# Laser_module_supply.net
KiCad netlist of a schematic drawn in Altium Designer
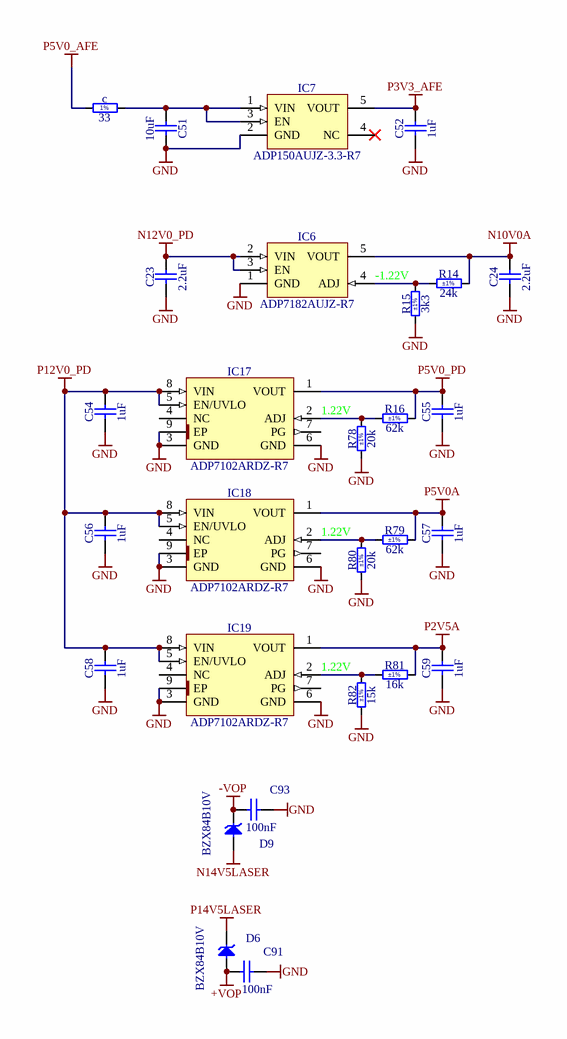
[diagram p0: Laser_module_supply.schdoc]

(export (version "E")
  (design (tool "Eeschema 10.0.6"))
  (components
    (comp (ref "c")
      (value "33")
      (footprint "RESC1005X40N")
      (description "Resistor - 1%")
      (fields
        (field (name "PART NUMBER") "R0402_33R_1%_0.0625W_100PPM")
        (field (name "POWER") "0.0625W")
        (field (name "AUTHOR") "CERN DEM JLC")
      )
      (libsource (lib "Resistors") (part "Resistor - 1%"))
    )
    (comp (ref "C23")
      (value "2.2uF")
      (footprint "CAPC2012X135N")
      (description "Non-polarised capacitor")
      (fields
        (field (name "PART NUMBER") "CC0805_2.2UF_16V_10%_X7R")
        (field (name "VOLTAGE") "16V")
        (field (name "AUTHOR") "CERN DEM JLC")
      )
      (libsource (lib "Capacitors") (part "Capacitor - non polarized"))
    )
    (comp (ref "C24")
      (value "2.2uF")
      (footprint "CAPC2012X135N")
      (description "Non-polarised capacitor")
      (fields
        (field (name "PART NUMBER") "CC0805_2.2UF_16V_10%_X7R")
        (field (name "VOLTAGE") "16V")
        (field (name "AUTHOR") "CERN DEM JLC")
      )
      (libsource (lib "Capacitors") (part "Capacitor - non polarized"))
    )
    (comp (ref "C51")
      (value "10uF")
      (footprint "CAPC2012X135N")
      (description "Non-polarised capacitor")
      (fields
        (field (name "PART NUMBER") "CC0805_10UF_16V_10%_X5R")
        (field (name "VOLTAGE") "16V")
        (field (name "AUTHOR") "CERN DEM JLC")
      )
      (libsource (lib "Capacitors") (part "Capacitor - non polarized"))
    )
    (comp (ref "C52")
      (value "1uF")
      (footprint "CAPC1608X87N")
      (description "Non-polarised capacitor")
      (fields
        (field (name "PART NUMBER") "CC0603_1UF_25V_10%_X7R")
        (field (name "VOLTAGE") "25V")
        (field (name "AUTHOR") "CERN DEM JLC")
      )
      (libsource (lib "Capacitors") (part "Capacitor - non polarized"))
    )
    (comp (ref "C54")
      (value "1uF")
      (footprint "CAPC1608X87N")
      (description "Non-polarised capacitor")
      (fields
        (field (name "PART NUMBER") "CC0603_1UF_25V_10%_X7R")
        (field (name "VOLTAGE") "25V")
        (field (name "AUTHOR") "CERN DEM JLC")
      )
      (libsource (lib "Capacitors") (part "Capacitor - non polarized"))
    )
    (comp (ref "C55")
      (value "1uF")
      (footprint "CAPC1608X87N")
      (description "Non-polarised capacitor")
      (fields
        (field (name "PART NUMBER") "CC0603_1UF_25V_10%_X7R")
        (field (name "VOLTAGE") "25V")
        (field (name "AUTHOR") "CERN DEM JLC")
      )
      (libsource (lib "Capacitors") (part "Capacitor - non polarized"))
    )
    (comp (ref "C56")
      (value "1uF")
      (footprint "CAPC1608X87N")
      (description "Non-polarised capacitor")
      (fields
        (field (name "PART NUMBER") "CC0603_1UF_25V_10%_X7R")
        (field (name "VOLTAGE") "25V")
        (field (name "AUTHOR") "CERN DEM JLC")
      )
      (libsource (lib "Capacitors") (part "Capacitor - non polarized"))
    )
    (comp (ref "C57")
      (value "1uF")
      (footprint "CAPC1608X87N")
      (description "Non-polarised capacitor")
      (fields
        (field (name "PART NUMBER") "CC0603_1UF_25V_10%_X7R")
        (field (name "VOLTAGE") "25V")
        (field (name "AUTHOR") "CERN DEM JLC")
      )
      (libsource (lib "Capacitors") (part "Capacitor - non polarized"))
    )
    (comp (ref "C58")
      (value "1uF")
      (footprint "CAPC1608X87N")
      (description "Non-polarised capacitor")
      (fields
        (field (name "PART NUMBER") "CC0603_1UF_25V_10%_X7R")
        (field (name "VOLTAGE") "25V")
        (field (name "AUTHOR") "CERN DEM JLC")
      )
      (libsource (lib "Capacitors") (part "Capacitor - non polarized"))
    )
    (comp (ref "C59")
      (value "1uF")
      (footprint "CAPC1608X87N")
      (description "Non-polarised capacitor")
      (fields
        (field (name "PART NUMBER") "CC0603_1UF_25V_10%_X7R")
        (field (name "VOLTAGE") "25V")
        (field (name "AUTHOR") "CERN DEM JLC")
      )
      (libsource (lib "Capacitors") (part "Capacitor - non polarized"))
    )
    (comp (ref "C91")
      (value "100nF")
      (footprint "CAPC1608X87N")
      (description "Non-polarised capacitor")
      (fields
        (field (name "PART NUMBER") "CC0603_100NF_50V_10%_X7R")
        (field (name "VOLTAGE") "50V")
        (field (name "AUTHOR") "CERN DEM JLC")
      )
      (libsource (lib "Capacitors") (part "Capacitor - non polarized"))
    )
    (comp (ref "C93")
      (value "100nF")
      (footprint "CAPC1608X87N")
      (description "Non-polarised capacitor")
      (fields
        (field (name "PART NUMBER") "CC0603_100NF_50V_10%_X7R")
        (field (name "VOLTAGE") "50V")
        (field (name "AUTHOR") "CERN DEM JLC")
      )
      (libsource (lib "Capacitors") (part "Capacitor - non polarized"))
    )
    (comp (ref "D6")
      (value "BZX84B10V")
      (footprint "SOT95P248X115-3N")
      (description "Diode Zener Anode Pin 1 Cathode Pin 3 (Pas de pin 2)")
      (fields
        (field (name "VOLTAGE") "10V")
        (field (name "POWER") "300mW")
        (field (name "AUTHOR") "CERN DEM JLC")
      )
      (libsource (lib "ICs And Semiconductors") (part "Diode Zener A1C3"))
    )
    (comp (ref "D9")
      (value "BZX84B10V")
      (footprint "SOT95P248X115-3N")
      (description "Diode Zener Anode Pin 1 Cathode Pin 3 (Pas de pin 2)")
      (fields
        (field (name "VOLTAGE") "10V")
        (field (name "POWER") "300mW")
        (field (name "AUTHOR") "CERN DEM JLC")
      )
      (libsource (lib "ICs And Semiconductors") (part "Diode Zener A1C3"))
    )
    (comp (ref "IC6")
      (value "ADP7182AUJZ-R7")
      (footprint "SOT95P280X90-5N")
      (description "-1.22V to -27V, -200mA, Adjustable, Low Noise, Negative Linear Regulator")
      (fields (field (name "MANUFACTURER") "ANALOG DEVICES") (field (name "AUTHOR") "CERN DEM JLC"))
      (libsource (lib "ICs And Semiconductors") (part "ADP7182AUJZ-R7"))
    )
    (comp (ref "IC7")
      (value "ADP150AUJZ-3.3-R7")
      (footprint "SOT95P280X90-5N")
      (description "Ultralow Noise, 150 mA CMOS Linear Regulator")
      (fields (field (name "MANUFACTURER") "ANALOG DEVICES") (field (name "AUTHOR") "CERN DEM JLC"))
      (libsource (lib "ICs And Semiconductors") (part "ADP150AUJZ"))
    )
    (comp (ref "IC17")
      (value "ADP7102ARDZ-R7")
      (footprint "SOIC127P600X175-9N-R241X309")
      (description "1.22V to 19V, 300mA, Low Noise, CMOS LDO Adjustable Linear Regulator")
      (fields
        (field (name "MANUFACTURER") "ANALOG DEVICES")
        (field (name "MANUFACTURER PART NUMBER") "ADP7102ARD")
        (field (name "AUTHOR") "CERN DEM JLC")
      )
      (libsource (lib "ICs And Semiconductors") (part "ADP7102ARDZ-R7"))
    )
    (comp (ref "IC18")
      (value "ADP7102ARDZ-R7")
      (footprint "SOIC127P600X175-9N-R241X309")
      (description "1.22V to 19V, 300mA, Low Noise, CMOS LDO Adjustable Linear Regulator")
      (fields
        (field (name "MANUFACTURER") "ANALOG DEVICES")
        (field (name "MANUFACTURER PART NUMBER") "ADP7102ARD")
        (field (name "AUTHOR") "CERN DEM JLC")
      )
      (libsource (lib "ICs And Semiconductors") (part "ADP7102ARDZ-R7"))
    )
    (comp (ref "IC19")
      (value "ADP7102ARDZ-R7")
      (footprint "SOIC127P600X175-9N-R241X309")
      (description "1.22V to 19V, 300mA, Low Noise, CMOS LDO Adjustable Linear Regulator")
      (fields
        (field (name "MANUFACTURER") "ANALOG DEVICES")
        (field (name "MANUFACTURER PART NUMBER") "ADP7102ARD")
        (field (name "AUTHOR") "CERN DEM JLC")
      )
      (libsource (lib "ICs And Semiconductors") (part "ADP7102ARDZ-R7"))
    )
    (comp (ref "R14")
      (value "24k")
      (footprint "RESC1005X40N")
      (description "Resistor - 1%")
      (fields
        (field (name "TOLERANCE") "±1%")
        (field (name "PART NUMBER") "R0402_24K_1%_0.0625W_100PPM")
        (field (name "POWER") "0.0625W")
        (field (name "AUTHOR") "CERN DEM JLC")
      )
      (libsource (lib "Resistors") (part "Resistor - 1%"))
    )
    (comp (ref "R15")
      (value "3k3")
      (footprint "RESC1005X40N")
      (description "Resistor - 1%")
      (fields
        (field (name "TOLERANCE") "±1%")
        (field (name "PART NUMBER") "R0402_3K3_1%_0.0625W_100PPM")
        (field (name "POWER") "0.0625W")
        (field (name "AUTHOR") "CERN DEM JLC")
      )
      (libsource (lib "Resistors") (part "Resistor - 1%"))
    )
    (comp (ref "R16")
      (value "62k")
      (footprint "RESC1005X40N")
      (description "Resistor - 1%")
      (fields
        (field (name "TOLERANCE") "±1%")
        (field (name "PART NUMBER") "R0402_62K_1%_0.0625W_100PPM")
        (field (name "POWER") "0.0625W")
        (field (name "AUTHOR") "CERN DEM JLC")
      )
      (libsource (lib "Resistors") (part "Resistor - 1%"))
    )
    (comp (ref "R78")
      (value "20k")
      (footprint "RESC1005X40N")
      (description "Resistor - 1%")
      (fields
        (field (name "TOLERANCE") "±1%")
        (field (name "PART NUMBER") "R0402_20K_1%_0.0625W_100PPM")
        (field (name "POWER") "0.0625W")
        (field (name "AUTHOR") "CERN DEM JLC")
      )
      (libsource (lib "Resistors") (part "Resistor - 1%"))
    )
    (comp (ref "R79")
      (value "62k")
      (footprint "RESC1005X40N")
      (description "Resistor - 1%")
      (fields
        (field (name "TOLERANCE") "±1%")
        (field (name "PART NUMBER") "R0402_62K_1%_0.0625W_100PPM")
        (field (name "POWER") "0.0625W")
        (field (name "AUTHOR") "CERN DEM JLC")
      )
      (libsource (lib "Resistors") (part "Resistor - 1%"))
    )
    (comp (ref "R80")
      (value "20k")
      (footprint "RESC1005X40N")
      (description "Resistor - 1%")
      (fields
        (field (name "TOLERANCE") "±1%")
        (field (name "PART NUMBER") "R0402_20K_1%_0.0625W_100PPM")
        (field (name "POWER") "0.0625W")
        (field (name "AUTHOR") "CERN DEM JLC")
      )
      (libsource (lib "Resistors") (part "Resistor - 1%"))
    )
    (comp (ref "R81")
      (value "16k")
      (footprint "RESC1005X40N")
      (description "Resistor - 1%")
      (fields
        (field (name "TOLERANCE") "±1%")
        (field (name "PART NUMBER") "R0402_16K_1%_0.0625W_100PPM")
        (field (name "POWER") "0.0625W")
        (field (name "AUTHOR") "CERN DEM JLC")
      )
      (libsource (lib "Resistors") (part "Resistor - 1%"))
    )
    (comp (ref "R82")
      (value "15k")
      (footprint "RESC1005X40N")
      (description "Resistor - 1%")
      (fields
        (field (name "TOLERANCE") "±1%")
        (field (name "PART NUMBER") "R0402_15K_1%_0.0625W_100PPM")
        (field (name "POWER") "0.0625W")
        (field (name "AUTHOR") "CERN DEM JMW")
      )
      (libsource (lib "Resistors") (part "Resistor - 1%"))
    )
  )
  (nets
    (net (code "1") (name "+VOP") (class "Default")
      (node (ref "C91") (pin "1") (pinfunction "1_1") (pintype "passive"))
      (node (ref "D6") (pin "1") (pinfunction "A_1") (pintype "passive"))
    )
    (net (code "2") (name "-VOP") (class "Default")
      (node (ref "C93") (pin "1") (pinfunction "1_1") (pintype "passive"))
      (node (ref "D9") (pin "3") (pinfunction "C_3") (pintype "passive"))
    )
    (net (code "3") (name "GND") (class "Default")
      (node (ref "C23") (pin "1") (pinfunction "1_1") (pintype "passive"))
      (node (ref "C24") (pin "1") (pinfunction "1_1") (pintype "passive"))
      (node (ref "C51") (pin "2") (pinfunction "2_2") (pintype "passive"))
      (node (ref "C52") (pin "1") (pinfunction "1_1") (pintype "passive"))
      (node (ref "C54") (pin "1") (pinfunction "1_1") (pintype "passive"))
      (node (ref "C55") (pin "1") (pinfunction "1_1") (pintype "passive"))
      (node (ref "C56") (pin "1") (pinfunction "1_1") (pintype "passive"))
      (node (ref "C57") (pin "1") (pinfunction "1_1") (pintype "passive"))
      (node (ref "C58") (pin "1") (pinfunction "1_1") (pintype "passive"))
      (node (ref "C59") (pin "1") (pinfunction "1_1") (pintype "passive"))
      (node (ref "C91") (pin "2") (pinfunction "2_2") (pintype "passive"))
      (node (ref "C93") (pin "2") (pinfunction "2_2") (pintype "passive"))
      (node (ref "IC17") (pin "3") (pinfunction "GND_3") (pintype "power_in"))
      (node (ref "IC17") (pin "6") (pinfunction "GND_6") (pintype "power_in"))
      (node (ref "IC17") (pin "9") (pinfunction "EP_9") (pintype "power_in"))
      (node (ref "IC18") (pin "3") (pinfunction "GND_3") (pintype "power_in"))
      (node (ref "IC18") (pin "6") (pinfunction "GND_6") (pintype "power_in"))
      (node (ref "IC18") (pin "9") (pinfunction "EP_9") (pintype "power_in"))
      (node (ref "IC19") (pin "3") (pinfunction "GND_3") (pintype "power_in"))
      (node (ref "IC19") (pin "6") (pinfunction "GND_6") (pintype "power_in"))
      (node (ref "IC19") (pin "9") (pinfunction "EP_9") (pintype "power_in"))
      (node (ref "IC6") (pin "1") (pinfunction "GND_1") (pintype "power_in"))
      (node (ref "IC7") (pin "2") (pinfunction "GND_2") (pintype "power_in"))
      (node (ref "R15") (pin "1") (pinfunction "1_1") (pintype "passive"))
      (node (ref "R78") (pin "1") (pinfunction "1_1") (pintype "passive"))
      (node (ref "R80") (pin "1") (pinfunction "1_1") (pintype "passive"))
      (node (ref "R82") (pin "1") (pinfunction "1_1") (pintype "passive"))
    )
    (net (code "4") (name "N10V0A") (class "Default")
      (node (ref "C24") (pin "2") (pinfunction "2_2") (pintype "passive"))
      (node (ref "IC6") (pin "5") (pinfunction "VOUT_5") (pintype "power_in"))
      (node (ref "R14") (pin "2") (pinfunction "2_2") (pintype "passive"))
    )
    (net (code "5") (name "N12V0_PD") (class "Default")
      (node (ref "C23") (pin "2") (pinfunction "2_2") (pintype "passive"))
      (node (ref "IC6") (pin "2") (pinfunction "VIN_2") (pintype "input"))
      (node (ref "IC6") (pin "3") (pinfunction "EN_3") (pintype "input"))
    )
    (net (code "6") (name "N14V5LASER") (class "Default")
      (node (ref "D9") (pin "1") (pinfunction "A_1") (pintype "passive"))
    )
    (net (code "7") (name "Net-(IC6-ADJ)") (class "Default")
      (node (ref "IC6") (pin "4") (pinfunction "ADJ_4") (pintype "input"))
      (node (ref "R14") (pin "1") (pinfunction "1_1") (pintype "passive"))
      (node (ref "R15") (pin "2") (pinfunction "2_2") (pintype "passive"))
    )
    (net (code "8") (name "Net-(IC7-EN)") (class "Default")
      (node (ref "C51") (pin "1") (pinfunction "1_1") (pintype "passive"))
      (node (ref "IC7") (pin "1") (pinfunction "VIN_1") (pintype "input"))
      (node (ref "IC7") (pin "3") (pinfunction "EN_3") (pintype "input"))
      (node (ref "c") (pin "2") (pinfunction "2_2") (pintype "passive"))
    )
    (net (code "9") (name "Net-(IC17-ADJ)") (class "Default")
      (node (ref "IC17") (pin "2") (pinfunction "ADJ_2") (pintype "input"))
      (node (ref "R16") (pin "1") (pinfunction "1_1") (pintype "passive"))
      (node (ref "R78") (pin "2") (pinfunction "2_2") (pintype "passive"))
    )
    (net (code "10") (name "Net-(IC18-ADJ)") (class "Default")
      (node (ref "IC18") (pin "2") (pinfunction "ADJ_2") (pintype "input"))
      (node (ref "R79") (pin "1") (pinfunction "1_1") (pintype "passive"))
      (node (ref "R80") (pin "2") (pinfunction "2_2") (pintype "passive"))
    )
    (net (code "11") (name "Net-(IC19-ADJ)") (class "Default")
      (node (ref "IC19") (pin "2") (pinfunction "ADJ_2") (pintype "input"))
      (node (ref "R81") (pin "1") (pinfunction "1_1") (pintype "passive"))
      (node (ref "R82") (pin "2") (pinfunction "2_2") (pintype "passive"))
    )
    (net (code "12") (name "P2V5A") (class "Default")
      (node (ref "C59") (pin "2") (pinfunction "2_2") (pintype "passive"))
      (node (ref "IC19") (pin "1") (pinfunction "VOUT_1") (pintype "power_in"))
      (node (ref "R81") (pin "2") (pinfunction "2_2") (pintype "passive"))
    )
    (net (code "13") (name "P3V3_AFE") (class "Default")
      (node (ref "C52") (pin "2") (pinfunction "2_2") (pintype "passive"))
      (node (ref "IC7") (pin "5") (pinfunction "VOUT_5") (pintype "power_in"))
    )
    (net (code "14") (name "P5V0A") (class "Default")
      (node (ref "C57") (pin "2") (pinfunction "2_2") (pintype "passive"))
      (node (ref "IC18") (pin "1") (pinfunction "VOUT_1") (pintype "power_in"))
      (node (ref "R79") (pin "2") (pinfunction "2_2") (pintype "passive"))
    )
    (net (code "15") (name "P5V0_AFE") (class "Default")
      (node (ref "c") (pin "1") (pinfunction "1_1") (pintype "passive"))
    )
    (net (code "16") (name "P5V0_PD") (class "Default")
      (node (ref "C55") (pin "2") (pinfunction "2_2") (pintype "passive"))
      (node (ref "IC17") (pin "1") (pinfunction "VOUT_1") (pintype "power_in"))
      (node (ref "R16") (pin "2") (pinfunction "2_2") (pintype "passive"))
    )
    (net (code "17") (name "P12V0_PD") (class "Default")
      (node (ref "C54") (pin "2") (pinfunction "2_2") (pintype "passive"))
      (node (ref "C56") (pin "2") (pinfunction "2_2") (pintype "passive"))
      (node (ref "C58") (pin "2") (pinfunction "2_2") (pintype "passive"))
      (node (ref "IC17") (pin "5") (pinfunction "EN/UVLO_5") (pintype "input"))
      (node (ref "IC17") (pin "8") (pinfunction "VIN_8") (pintype "input"))
      (node (ref "IC18") (pin "5") (pinfunction "EN/UVLO_5") (pintype "input"))
      (node (ref "IC18") (pin "8") (pinfunction "VIN_8") (pintype "input"))
      (node (ref "IC19") (pin "5") (pinfunction "EN/UVLO_5") (pintype "input"))
      (node (ref "IC19") (pin "8") (pinfunction "VIN_8") (pintype "input"))
    )
    (net (code "18") (name "P14V5LASER") (class "Default")
      (node (ref "D6") (pin "3") (pinfunction "C_3") (pintype "passive"))
    )
    (net (code "19") (name "unconnected-(IC7-NC-Pad4)") (class "Default")
      (node (ref "IC7") (pin "4") (pinfunction "NC_4") (pintype "passive+no_connect"))
    )
    (net (code "20") (name "unconnected-(IC17-NC-Pad4)") (class "Default")
      (node (ref "IC17") (pin "4") (pinfunction "NC_4") (pintype "passive"))
    )
    (net (code "21") (name "unconnected-(IC17-PG-Pad7)") (class "Default")
      (node (ref "IC17") (pin "7") (pinfunction "PG_7") (pintype "output"))
    )
    (net (code "22") (name "unconnected-(IC18-NC-Pad4)") (class "Default")
      (node (ref "IC18") (pin "4") (pinfunction "NC_4") (pintype "passive"))
    )
    (net (code "23") (name "unconnected-(IC18-PG-Pad7)") (class "Default")
      (node (ref "IC18") (pin "7") (pinfunction "PG_7") (pintype "output"))
    )
    (net (code "24") (name "unconnected-(IC19-NC-Pad4)") (class "Default")
      (node (ref "IC19") (pin "4") (pinfunction "NC_4") (pintype "passive"))
    )
    (net (code "25") (name "unconnected-(IC19-PG-Pad7)") (class "Default")
      (node (ref "IC19") (pin "7") (pinfunction "PG_7") (pintype "output"))
    )
  )
)
